# STM32.net
KiCad netlist of a schematic drawn in Altium Designer
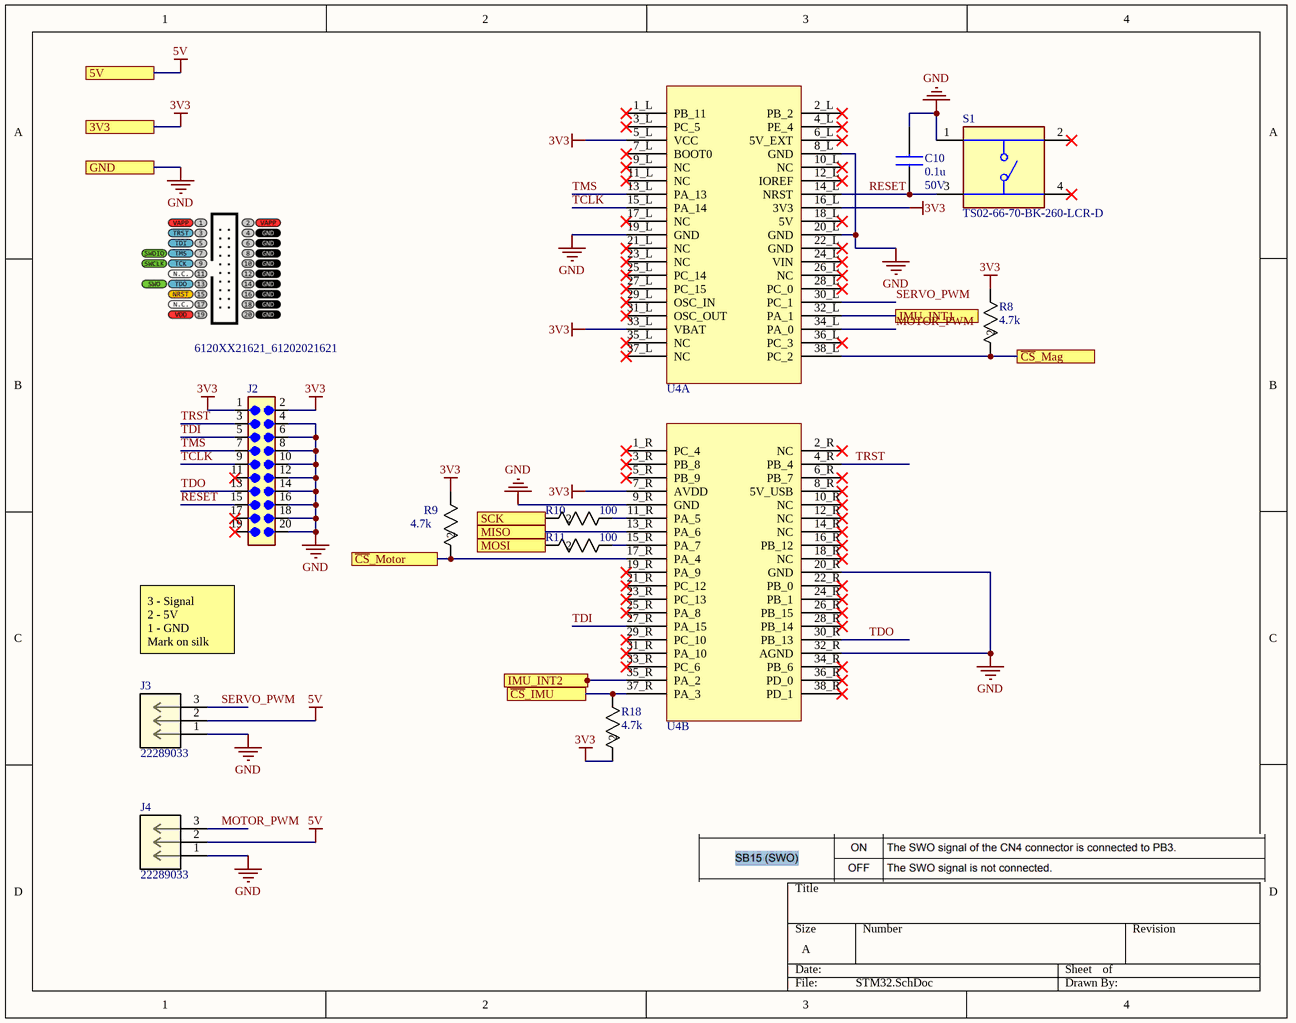
[diagram p0: STM32.SchDoc]

(export (version "E")
  (design (tool "Eeschema 10.0.6"))
  (components
    (comp (ref "C10")
      (value "0.1u")
      (footprint "CAPC2012X145N")
      (description "Multilayer Ceramic Chip Capacitors, Capacitance=0.1u")
      (fields
        (field (name "MANUFACTURER_PART_NUMBER") "KAM21BR71H104JM")
        (field (name "RATED VOLTAGE") "50V")
      )
      (libsource (lib "Caps") (part "KAM21BR71H104JM"))
    )
    (comp (ref "J2")
      (value "6120XX21621_61202021621")
      (footprint "61202021621")
      (fields
        (field (name "MF") "{'manufacturer': u'~{W}xfcrth Elektronik'}")
        (field (name "MP") "61202021621")
      )
      (libsource (lib "6120XX21621_61202021621") (part "6120XX21621_61202021621"))
    )
    (comp (ref "J3")
      (value "22289033")
      (footprint "CONN03_22289033_MOL")
      (fields (field (name "COPYRIGHT") "Copyright (C) 2025 Ultra Librarian. All rights reserved."))
      (libsource (lib "22289033") (part "22289033"))
    )
    (comp (ref "J4")
      (value "22289033")
      (footprint "CONN03_22289033_MOL")
      (fields (field (name "COPYRIGHT") "Copyright (C) 2025 Ultra Librarian. All rights reserved."))
      (libsource (lib "22289033") (part "22289033"))
    )
    (comp (ref "R8")
      (value "4.7k")
      (footprint "RC0805N_YAG")
      (description "RES 0805 4.7k 5% 1/8W")
      (fields (field (name "MANUFACTURER_PART_NUMBER") "RC0805JR-074K7L") (field (name "TOLERANCE") "5%"))
      (libsource (lib "Resistors") (part "RC0805JR-074K7L"))
    )
    (comp (ref "R9")
      (value "4.7k")
      (footprint "RC0805N_YAG")
      (description "RES 0805 4.7k 5% 1/8W")
      (fields (field (name "MANUFACTURER_PART_NUMBER") "RC0805JR-074K7L") (field (name "TOLERANCE") "5%"))
      (libsource (lib "Resistors") (part "RC0805JR-074K7L"))
    )
    (comp (ref "R10")
      (value "100")
      (footprint "RC0805N_YAG")
      (description "RES 0805 100 5% 1/8W")
      (fields (field (name "MANUFACTURER_PART_NUMBER") "RC0805JR-07100RL") (field (name "TOLERANCE") "5%"))
      (libsource (lib "Resistors") (part "RC0805JR-07100RL"))
    )
    (comp (ref "R11")
      (value "100")
      (footprint "RC0805N_YAG")
      (description "RES 0805 100 5% 1/8W")
      (fields (field (name "MANUFACTURER_PART_NUMBER") "RC0805JR-07100RL") (field (name "TOLERANCE") "5%"))
      (libsource (lib "Resistors") (part "RC0805JR-07100RL"))
    )
    (comp (ref "R18")
      (value "4.7k")
      (footprint "RC0805N_YAG")
      (description "RES 0805 4.7k 5% 1/8W")
      (fields (field (name "MANUFACTURER_PART_NUMBER") "RC0805JR-074K7L") (field (name "TOLERANCE") "5%"))
      (libsource (lib "Resistors") (part "RC0805JR-074K7L"))
    )
    (comp (ref "S1")
      (value "TS02-66-70-BK-260-LCR-D")
      (footprint "SW_TS02-66-70-BK-260-LCR-D")
      (description "6 x 6 mm, 7 mm Actuator Height, 260 gf, Black, Long Crimped, Through Hole, SPST, Tactile Switch")
      (fields (field (name "MF") "Same Sky"))
      (libsource (lib "TS02-66-70-BK-260-LCR-D") (part "TS02-66-70-BK-260-LCR-D"))
    )
    (comp (ref "U4")
      (value "STM32_WB55")
      (footprint "PCBComponent_1")
      (libsource (lib "P_STM32_WB55") (part "STM32_WB55"))
    )
  )
  (nets
    (net (code "1") (name "/IMU_INT1") (class "Default")
      (node (ref "U4") (pin "32_L") (pinfunction "PA_1_32_L") (pintype "passive"))
    )
    (net (code "2") (name "/IMU_INT2") (class "Default")
      (node (ref "U4") (pin "35_R") (pinfunction "PA_2_35_R") (pintype "passive"))
    )
    (net (code "3") (name "/MISO") (class "Default")
      (node (ref "U4") (pin "13_R") (pinfunction "PA_6_13_R") (pintype "passive"))
    )
    (net (code "4") (name "/MOSI") (class "Default")
      (node (ref "R11") (pin "2") (pinfunction "2_2") (pintype "passive"))
    )
    (net (code "5") (name "/MOTOR_PWM") (class "Default")
      (node (ref "J4") (pin "3") (pinfunction "3_3") (pintype "passive"))
      (node (ref "U4") (pin "34_L") (pinfunction "PA_0_34_L") (pintype "passive"))
    )
    (net (code "6") (name "/RESET") (class "Default")
      (node (ref "C10") (pin "1") (pinfunction "1_1") (pintype "passive"))
      (node (ref "J2") (pin "15") (pinfunction "15_15") (pintype "passive"))
      (node (ref "S1") (pin "3") (pinfunction "3_3") (pintype "passive"))
      (node (ref "U4") (pin "14_L") (pinfunction "NRST_14_L") (pintype "passive"))
    )
    (net (code "7") (name "/SCK") (class "Default")
      (node (ref "R10") (pin "2") (pinfunction "2_2") (pintype "passive"))
    )
    (net (code "8") (name "/SERVO_PWM") (class "Default")
      (node (ref "J3") (pin "3") (pinfunction "3_3") (pintype "passive"))
      (node (ref "U4") (pin "30_L") (pinfunction "PC_1_30_L") (pintype "passive"))
    )
    (net (code "9") (name "/TCLK") (class "Default")
      (node (ref "J2") (pin "9") (pinfunction "9_9") (pintype "passive"))
      (node (ref "U4") (pin "15_L") (pinfunction "PA_14_15_L") (pintype "passive"))
    )
    (net (code "10") (name "/TDI") (class "Default")
      (node (ref "J2") (pin "5") (pinfunction "5_5") (pintype "passive"))
      (node (ref "U4") (pin "27_R") (pinfunction "PA_15_27_R") (pintype "passive"))
    )
    (net (code "11") (name "/TDO") (class "Default")
      (node (ref "J2") (pin "13") (pinfunction "13_13") (pintype "passive"))
      (node (ref "U4") (pin "30_R") (pinfunction "PB_13_30_R") (pintype "passive"))
    )
    (net (code "12") (name "/TMS") (class "Default")
      (node (ref "J2") (pin "7") (pinfunction "7_7") (pintype "passive"))
      (node (ref "U4") (pin "13_L") (pinfunction "PA_13_13_L") (pintype "passive"))
    )
    (net (code "13") (name "/TRST") (class "Default")
      (node (ref "J2") (pin "3") (pinfunction "3_3") (pintype "passive"))
      (node (ref "U4") (pin "4_R") (pinfunction "PB_4_4_R") (pintype "passive"))
    )
    (net (code "14") (name "/~{CS}_IMU") (class "Default")
      (node (ref "R18") (pin "1") (pinfunction "1_1") (pintype "passive"))
      (node (ref "U4") (pin "37_R") (pinfunction "PA_3_37_R") (pintype "passive"))
    )
    (net (code "15") (name "/~{CS}_Mag") (class "Default")
      (node (ref "R8") (pin "2") (pinfunction "2_2") (pintype "passive"))
      (node (ref "U4") (pin "38_L") (pinfunction "PC_2_38_L") (pintype "passive"))
    )
    (net (code "16") (name "/~{CS}_Motor") (class "Default")
      (node (ref "R9") (pin "2") (pinfunction "2_2") (pintype "passive"))
      (node (ref "U4") (pin "17_R") (pinfunction "PA_4_17_R") (pintype "passive"))
    )
    (net (code "17") (name "3V3") (class "Default")
      (node (ref "J2") (pin "1") (pinfunction "1_1") (pintype "passive"))
      (node (ref "J2") (pin "2") (pinfunction "2_2") (pintype "passive"))
      (node (ref "R18") (pin "2") (pinfunction "2_2") (pintype "passive"))
      (node (ref "R8") (pin "1") (pinfunction "1_1") (pintype "passive"))
      (node (ref "R9") (pin "1") (pinfunction "1_1") (pintype "passive"))
      (node (ref "U4") (pin "16_L") (pinfunction "3V3_16_L") (pintype "passive"))
      (node (ref "U4") (pin "33_L") (pinfunction "VBAT_33_L") (pintype "passive"))
      (node (ref "U4") (pin "5_L") (pinfunction "VCC_5_L") (pintype "passive"))
      (node (ref "U4") (pin "7_R") (pinfunction "AVDD_7_R") (pintype "passive"))
    )
    (net (code "18") (name "5V") (class "Default")
      (node (ref "J3") (pin "2") (pinfunction "2_2") (pintype "passive"))
      (node (ref "J4") (pin "2") (pinfunction "2_2") (pintype "passive"))
    )
    (net (code "19") (name "GND") (class "Default")
      (node (ref "C10") (pin "2") (pinfunction "2_2") (pintype "passive"))
      (node (ref "J2") (pin "10") (pinfunction "10_10") (pintype "passive"))
      (node (ref "J2") (pin "12") (pinfunction "12_12") (pintype "passive"))
      (node (ref "J2") (pin "14") (pinfunction "14_14") (pintype "passive"))
      (node (ref "J2") (pin "16") (pinfunction "16_16") (pintype "passive"))
      (node (ref "J2") (pin "18") (pinfunction "18_18") (pintype "passive"))
      (node (ref "J2") (pin "20") (pinfunction "20_20") (pintype "passive"))
      (node (ref "J2") (pin "4") (pinfunction "4_4") (pintype "passive"))
      (node (ref "J2") (pin "6") (pinfunction "6_6") (pintype "passive"))
      (node (ref "J2") (pin "8") (pinfunction "8_8") (pintype "passive"))
      (node (ref "J3") (pin "1") (pinfunction "1_1") (pintype "passive"))
      (node (ref "J4") (pin "1") (pinfunction "1_1") (pintype "passive"))
      (node (ref "S1") (pin "1") (pinfunction "1_1") (pintype "passive"))
      (node (ref "U4") (pin "19_L") (pinfunction "GND_19_L") (pintype "passive"))
      (node (ref "U4") (pin "20_L") (pinfunction "GND_20_L") (pintype "passive"))
      (node (ref "U4") (pin "20_R") (pinfunction "GND_20_R") (pintype "passive"))
      (node (ref "U4") (pin "32_R") (pinfunction "AGND_32_R") (pintype "passive"))
      (node (ref "U4") (pin "8_L") (pinfunction "GND_8_L") (pintype "passive"))
      (node (ref "U4") (pin "9_R") (pinfunction "GND_9_R") (pintype "passive"))
    )
    (net (code "20") (name "Net-(U4B-PA_5)") (class "Default")
      (node (ref "R10") (pin "1") (pinfunction "1_1") (pintype "passive"))
      (node (ref "U4") (pin "11_R") (pinfunction "PA_5_11_R") (pintype "passive"))
    )
    (net (code "21") (name "Net-(U4B-PA_7)") (class "Default")
      (node (ref "R11") (pin "1") (pinfunction "1_1") (pintype "passive"))
      (node (ref "U4") (pin "15_R") (pinfunction "PA_7_15_R") (pintype "passive"))
    )
    (net (code "22") (name "unconnected-(J2-Pad11)") (class "Default")
      (node (ref "J2") (pin "11") (pinfunction "11_11") (pintype "passive+no_connect"))
    )
    (net (code "23") (name "unconnected-(J2-Pad17)") (class "Default")
      (node (ref "J2") (pin "17") (pinfunction "17_17") (pintype "passive+no_connect"))
    )
    (net (code "24") (name "unconnected-(J2-Pad19)") (class "Default")
      (node (ref "J2") (pin "19") (pinfunction "19_19") (pintype "passive+no_connect"))
    )
    (net (code "25") (name "unconnected-(S1-Pad2)") (class "Default")
      (node (ref "S1") (pin "2") (pinfunction "2_2") (pintype "passive+no_connect"))
    )
    (net (code "26") (name "unconnected-(S1-Pad4)") (class "Default")
      (node (ref "S1") (pin "4") (pinfunction "4_4") (pintype "passive+no_connect"))
    )
    (net (code "27") (name "unconnected-(U4A-5V-Pad18_L)") (class "Default")
      (node (ref "U4") (pin "18_L") (pinfunction "5V_18_L") (pintype "passive+no_connect"))
    )
    (net (code "28") (name "unconnected-(U4A-5V_EXT-Pad6_L)") (class "Default")
      (node (ref "U4") (pin "6_L") (pinfunction "5V_EXT_6_L") (pintype "passive+no_connect"))
    )
    (net (code "29") (name "unconnected-(U4A-BOOT0-Pad7_L)") (class "Default")
      (node (ref "U4") (pin "7_L") (pinfunction "BOOT0_7_L") (pintype "passive+no_connect"))
    )
    (net (code "30") (name "unconnected-(U4A-GND-Pad22_L)") (class "Default")
      (node (ref "U4") (pin "22_L") (pinfunction "GND_22_L") (pintype "passive+no_connect"))
    )
    (net (code "31") (name "unconnected-(U4A-IOREF-Pad12_L)") (class "Default")
      (node (ref "U4") (pin "12_L") (pinfunction "IOREF_12_L") (pintype "passive+no_connect"))
    )
    (net (code "32") (name "unconnected-(U4A-NC-Pad9_L)") (class "Default")
      (node (ref "U4") (pin "9_L") (pinfunction "NC_9_L") (pintype "passive+no_connect"))
    )
    (net (code "33") (name "unconnected-(U4A-NC-Pad10_L)") (class "Default")
      (node (ref "U4") (pin "10_L") (pinfunction "NC_10_L") (pintype "passive+no_connect"))
    )
    (net (code "34") (name "unconnected-(U4A-NC-Pad11_L)") (class "Default")
      (node (ref "U4") (pin "11_L") (pinfunction "NC_11_L") (pintype "passive+no_connect"))
    )
    (net (code "35") (name "unconnected-(U4A-NC-Pad17_L)") (class "Default")
      (node (ref "U4") (pin "17_L") (pinfunction "NC_17_L") (pintype "passive+no_connect"))
    )
    (net (code "36") (name "unconnected-(U4A-NC-Pad21_L)") (class "Default")
      (node (ref "U4") (pin "21_L") (pinfunction "NC_21_L") (pintype "passive+no_connect"))
    )
    (net (code "37") (name "unconnected-(U4A-NC-Pad23_L)") (class "Default")
      (node (ref "U4") (pin "23_L") (pinfunction "NC_23_L") (pintype "passive+no_connect"))
    )
    (net (code "38") (name "unconnected-(U4A-NC-Pad26_L)") (class "Default")
      (node (ref "U4") (pin "26_L") (pinfunction "NC_26_L") (pintype "passive+no_connect"))
    )
    (net (code "39") (name "unconnected-(U4A-NC-Pad35_L)") (class "Default")
      (node (ref "U4") (pin "35_L") (pinfunction "NC_35_L") (pintype "passive+no_connect"))
    )
    (net (code "40") (name "unconnected-(U4A-NC-Pad37_L)") (class "Default")
      (node (ref "U4") (pin "37_L") (pinfunction "NC_37_L") (pintype "passive+no_connect"))
    )
    (net (code "41") (name "unconnected-(U4A-OSC_IN-Pad29_L)") (class "Default")
      (node (ref "U4") (pin "29_L") (pinfunction "OSC_IN_29_L") (pintype "passive+no_connect"))
    )
    (net (code "42") (name "unconnected-(U4A-OSC_OUT-Pad31_L)") (class "Default")
      (node (ref "U4") (pin "31_L") (pinfunction "OSC_OUT_31_L") (pintype "passive+no_connect"))
    )
    (net (code "43") (name "unconnected-(U4A-PB_2-Pad2_L)") (class "Default")
      (node (ref "U4") (pin "2_L") (pinfunction "PB_2_2_L") (pintype "passive+no_connect"))
    )
    (net (code "44") (name "unconnected-(U4A-PB_11-Pad1_L)") (class "Default")
      (node (ref "U4") (pin "1_L") (pinfunction "PB_11_1_L") (pintype "passive+no_connect"))
    )
    (net (code "45") (name "unconnected-(U4A-PC_0-Pad28_L)") (class "Default")
      (node (ref "U4") (pin "28_L") (pinfunction "PC_0_28_L") (pintype "passive+no_connect"))
    )
    (net (code "46") (name "unconnected-(U4A-PC_3-Pad36_L)") (class "Default")
      (node (ref "U4") (pin "36_L") (pinfunction "PC_3_36_L") (pintype "passive+no_connect"))
    )
    (net (code "47") (name "unconnected-(U4A-PC_5-Pad3_L)") (class "Default")
      (node (ref "U4") (pin "3_L") (pinfunction "PC_5_3_L") (pintype "passive+no_connect"))
    )
    (net (code "48") (name "unconnected-(U4A-PC_14-Pad25_L)") (class "Default")
      (node (ref "U4") (pin "25_L") (pinfunction "PC_14_25_L") (pintype "passive+no_connect"))
    )
    (net (code "49") (name "unconnected-(U4A-PC_15-Pad27_L)") (class "Default")
      (node (ref "U4") (pin "27_L") (pinfunction "PC_15_27_L") (pintype "passive+no_connect"))
    )
    (net (code "50") (name "unconnected-(U4A-PE_4-Pad4_L)") (class "Default")
      (node (ref "U4") (pin "4_L") (pinfunction "PE_4_4_L") (pintype "passive+no_connect"))
    )
    (net (code "51") (name "unconnected-(U4A-VIN-Pad24_L)") (class "Default")
      (node (ref "U4") (pin "24_L") (pinfunction "VIN_24_L") (pintype "passive+no_connect"))
    )
    (net (code "52") (name "unconnected-(U4B-5V_USB-Pad8_R)") (class "Default")
      (node (ref "U4") (pin "8_R") (pinfunction "5V_USB_8_R") (pintype "passive+no_connect"))
    )
    (net (code "53") (name "unconnected-(U4B-NC-Pad2_R)") (class "Default")
      (node (ref "U4") (pin "2_R") (pinfunction "NC_2_R") (pintype "passive+no_connect"))
    )
    (net (code "54") (name "unconnected-(U4B-NC-Pad10_R)") (class "Default")
      (node (ref "U4") (pin "10_R") (pinfunction "NC_10_R") (pintype "passive+no_connect"))
    )
    (net (code "55") (name "unconnected-(U4B-NC-Pad12_R)") (class "Default")
      (node (ref "U4") (pin "12_R") (pinfunction "NC_12_R") (pintype "passive+no_connect"))
    )
    (net (code "56") (name "unconnected-(U4B-NC-Pad14_R)") (class "Default")
      (node (ref "U4") (pin "14_R") (pinfunction "NC_14_R") (pintype "passive+no_connect"))
    )
    (net (code "57") (name "unconnected-(U4B-NC-Pad18_R)") (class "Default")
      (node (ref "U4") (pin "18_R") (pinfunction "NC_18_R") (pintype "passive+no_connect"))
    )
    (net (code "58") (name "unconnected-(U4B-PA_8-Pad25_R)") (class "Default")
      (node (ref "U4") (pin "25_R") (pinfunction "PA_8_25_R") (pintype "passive+no_connect"))
    )
    (net (code "59") (name "unconnected-(U4B-PA_9-Pad19_R)") (class "Default")
      (node (ref "U4") (pin "19_R") (pinfunction "PA_9_19_R") (pintype "passive+no_connect"))
    )
    (net (code "60") (name "unconnected-(U4B-PA_10-Pad31_R)") (class "Default")
      (node (ref "U4") (pin "31_R") (pinfunction "PA_10_31_R") (pintype "passive+no_connect"))
    )
    (net (code "61") (name "unconnected-(U4B-PB_0-Pad22_R)") (class "Default")
      (node (ref "U4") (pin "22_R") (pinfunction "PB_0_22_R") (pintype "passive+no_connect"))
    )
    (net (code "62") (name "unconnected-(U4B-PB_1-Pad24_R)") (class "Default")
      (node (ref "U4") (pin "24_R") (pinfunction "PB_1_24_R") (pintype "passive+no_connect"))
    )
    (net (code "63") (name "unconnected-(U4B-PB_6-Pad34_R)") (class "Default")
      (node (ref "U4") (pin "34_R") (pinfunction "PB_6_34_R") (pintype "passive+no_connect"))
    )
    (net (code "64") (name "unconnected-(U4B-PB_7-Pad6_R)") (class "Default")
      (node (ref "U4") (pin "6_R") (pinfunction "PB_7_6_R") (pintype "passive+no_connect"))
    )
    (net (code "65") (name "unconnected-(U4B-PB_8-Pad3_R)") (class "Default")
      (node (ref "U4") (pin "3_R") (pinfunction "PB_8_3_R") (pintype "passive+no_connect"))
    )
    (net (code "66") (name "unconnected-(U4B-PB_9-Pad5_R)") (class "Default")
      (node (ref "U4") (pin "5_R") (pinfunction "PB_9_5_R") (pintype "passive+no_connect"))
    )
    (net (code "67") (name "unconnected-(U4B-PB_12-Pad16_R)") (class "Default")
      (node (ref "U4") (pin "16_R") (pinfunction "PB_12_16_R") (pintype "passive+no_connect"))
    )
    (net (code "68") (name "unconnected-(U4B-PB_14-Pad28_R)") (class "Default")
      (node (ref "U4") (pin "28_R") (pinfunction "PB_14_28_R") (pintype "passive+no_connect"))
    )
    (net (code "69") (name "unconnected-(U4B-PB_15-Pad26_R)") (class "Default")
      (node (ref "U4") (pin "26_R") (pinfunction "PB_15_26_R") (pintype "passive+no_connect"))
    )
    (net (code "70") (name "unconnected-(U4B-PC_4-Pad1_R)") (class "Default")
      (node (ref "U4") (pin "1_R") (pinfunction "PC_4_1_R") (pintype "passive+no_connect"))
    )
    (net (code "71") (name "unconnected-(U4B-PC_6-Pad33_R)") (class "Default")
      (node (ref "U4") (pin "33_R") (pinfunction "PC_6_33_R") (pintype "passive+no_connect"))
    )
    (net (code "72") (name "unconnected-(U4B-PC_10-Pad29_R)") (class "Default")
      (node (ref "U4") (pin "29_R") (pinfunction "PC_10_29_R") (pintype "passive+no_connect"))
    )
    (net (code "73") (name "unconnected-(U4B-PC_12-Pad21_R)") (class "Default")
      (node (ref "U4") (pin "21_R") (pinfunction "PC_12_21_R") (pintype "passive+no_connect"))
    )
    (net (code "74") (name "unconnected-(U4B-PC_13-Pad23_R)") (class "Default")
      (node (ref "U4") (pin "23_R") (pinfunction "PC_13_23_R") (pintype "passive+no_connect"))
    )
    (net (code "75") (name "unconnected-(U4B-PD_0-Pad36_R)") (class "Default")
      (node (ref "U4") (pin "36_R") (pinfunction "PD_0_36_R") (pintype "passive+no_connect"))
    )
    (net (code "76") (name "unconnected-(U4B-PD_1-Pad38_R)") (class "Default")
      (node (ref "U4") (pin "38_R") (pinfunction "PD_1_38_R") (pintype "passive+no_connect"))
    )
  )
)
